# rapidshark-half-assed-half-h-bridge-mk-2.net
KiCad netlist of a schematic drawn in EAGLE
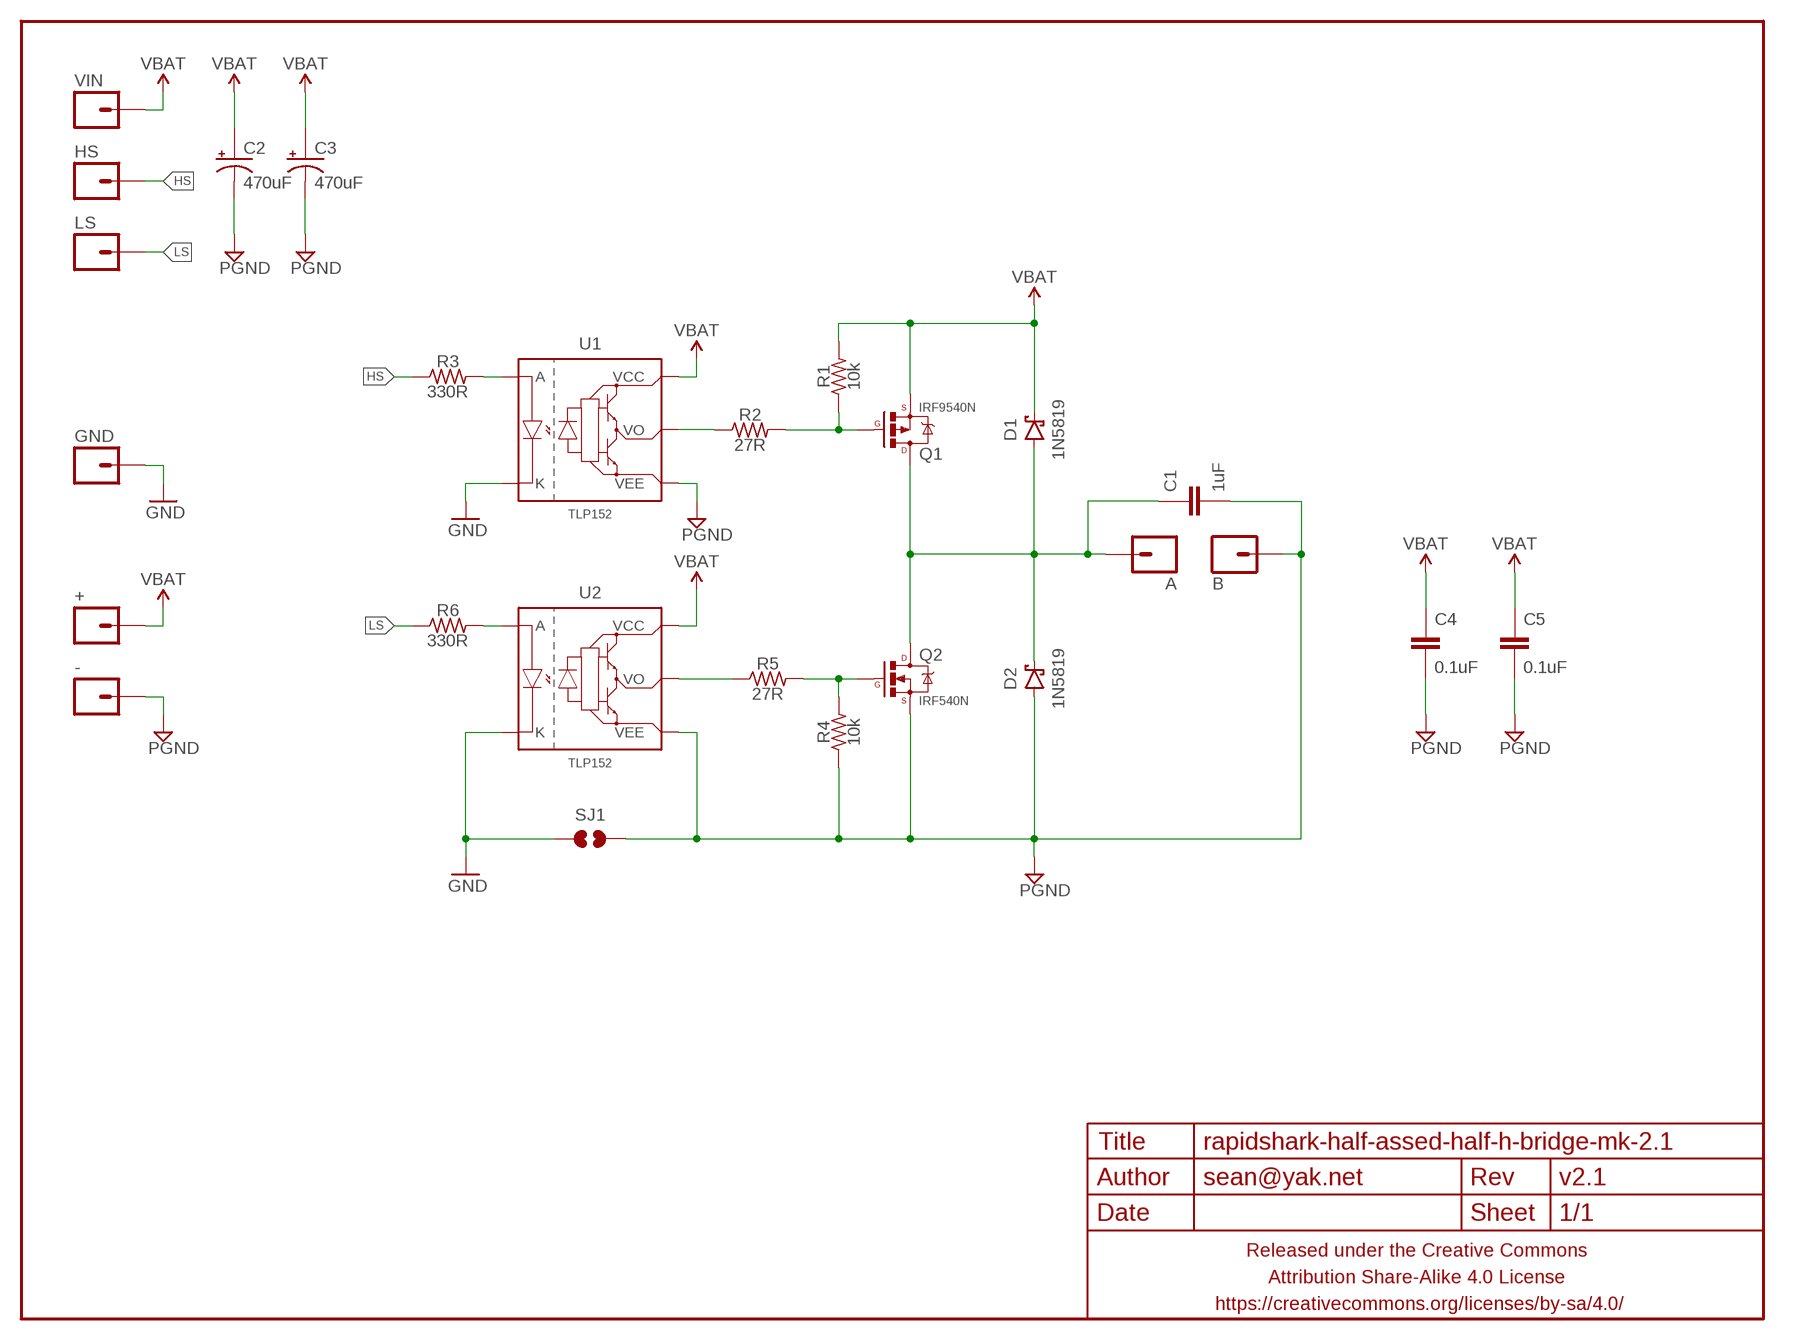
[diagram p0: schematic, sheet 1]

(export (version "E")
  (design (tool "Eeschema 10.0.6"))
  (components
    (comp (ref "+")
      (value "M01PTH-1.9MM")
      (footprint "eagle-import:1X01-1.9MM-CIR")
      (libsource (lib "eagle-import") (part "M01PTH-1.9MM"))
    )
    (comp (ref "-")
      (value "M01PTH-1.9MM")
      (footprint "eagle-import:1X01-1.9MM-CIR")
      (libsource (lib "eagle-import") (part "M01PTH-1.9MM"))
    )
    (comp (ref "A")
      (value "M01PTH-1.9MM")
      (footprint "eagle-import:1X01-1.9MM-CIR")
      (libsource (lib "eagle-import") (part "M01PTH-1.9MM"))
    )
    (comp (ref "B")
      (value "M01PTH-1.9MM")
      (footprint "eagle-import:1X01-1.9MM-CIR")
      (libsource (lib "eagle-import") (part "M01PTH-1.9MM"))
    )
    (comp (ref "C1")
      (value "1uF")
      (footprint "eagle-import:C0603-TIGHTER")
      (libsource (lib "eagle-import") (part "CAPACITOR-CERAMICC0603-TIGHTER"))
    )
    (comp (ref "C2")
      (value "470uF")
      (footprint "eagle-import:E5-10,5")
      (libsource (lib "eagle-import") (part "CAPACITOR-POLARIZEDE5-10.5"))
    )
    (comp (ref "C3")
      (value "470uF")
      (footprint "eagle-import:E5-10,5")
      (libsource (lib "eagle-import") (part "CAPACITOR-POLARIZEDE5-10.5"))
    )
    (comp (ref "C4")
      (value "0.1uF")
      (footprint "eagle-import:C0603-TIGHTER")
      (libsource (lib "eagle-import") (part "CAPACITOR-CERAMICC0603-TIGHTER"))
    )
    (comp (ref "C5")
      (value "0.1uF")
      (footprint "eagle-import:C0603-TIGHTER")
      (libsource (lib "eagle-import") (part "CAPACITOR-CERAMICC0603-TIGHTER"))
    )
    (comp (ref "D1")
      (value "1N5819")
      (footprint "eagle-import:SMA-DIODE-SCHOTTKY")
      (libsource (lib "eagle-import") (part "DIODE-SCHOTTKYSMA"))
    )
    (comp (ref "D2")
      (value "1N5819")
      (footprint "eagle-import:SMA-DIODE-SCHOTTKY")
      (libsource (lib "eagle-import") (part "DIODE-SCHOTTKYSMA"))
    )
    (comp (ref "FRAME1")
      (value "FRAME-LETTERNO_PACKAGE")
      (footprint "eagle-import:DUMMY")
      (fields (field (name "DESIGNER") "sean@yak.net") (field (name "VERSION") "v2.1"))
      (libsource (lib "eagle-import") (part "FRAME-LETTERNO_PACKAGE"))
    )
    (comp (ref "GND")
      (value "M01PTH")
      (footprint "eagle-import:1X01")
      (libsource (lib "eagle-import") (part "M01PTH"))
    )
    (comp (ref "HS")
      (value "M01PTH")
      (footprint "eagle-import:1X01")
      (libsource (lib "eagle-import") (part "M01PTH"))
    )
    (comp (ref "LS")
      (value "M01PTH")
      (footprint "eagle-import:1X01")
      (libsource (lib "eagle-import") (part "M01PTH"))
    )
    (comp (ref "Q1")
      (value "IRF9540N")
      (footprint "eagle-import:D2PAK")
      (libsource (lib "eagle-import") (part "MOSFET-PCHANNELD2PAK"))
    )
    (comp (ref "Q2")
      (value "IRF540N")
      (footprint "eagle-import:D2PAK")
      (libsource (lib "eagle-import") (part "MOSFET-NCHANNELD2PAK"))
    )
    (comp (ref "R1")
      (value "10k")
      (footprint "eagle-import:R0603-TIGHTER")
      (libsource (lib "eagle-import") (part "RESISTORR0603-TIGHTER"))
    )
    (comp (ref "R2")
      (value "27R")
      (footprint "eagle-import:R0603-TIGHTER")
      (libsource (lib "eagle-import") (part "RESISTORR0603-TIGHTER"))
    )
    (comp (ref "R3")
      (value "330R")
      (footprint "eagle-import:R0603-TIGHTER")
      (libsource (lib "eagle-import") (part "RESISTORR0603-TIGHTER"))
    )
    (comp (ref "R4")
      (value "10k")
      (footprint "eagle-import:R0603-TIGHTER")
      (libsource (lib "eagle-import") (part "RESISTORR0603-TIGHTER"))
    )
    (comp (ref "R5")
      (value "27R")
      (footprint "eagle-import:R0603-TIGHTER")
      (libsource (lib "eagle-import") (part "RESISTORR0603-TIGHTER"))
    )
    (comp (ref "R6")
      (value "330R")
      (footprint "eagle-import:R0603-TIGHTER")
      (libsource (lib "eagle-import") (part "RESISTORR0603-TIGHTER"))
    )
    (comp (ref "SJ1")
      (value "JUMPER-PAD-2-NO")
      (footprint "eagle-import:PAD-JUMPER-2-NO_NO_SILK")
      (libsource (lib "eagle-import") (part "JUMPER-PAD-2-NO"))
    )
    (comp (ref "U1")
      (value "TLP152")
      (footprint "eagle-import:SO05")
      (libsource (lib "eagle-import") (part "OPTOISOLATOR-GATEDRIVERSOIC05"))
    )
    (comp (ref "U2")
      (value "TLP152")
      (footprint "eagle-import:SO05")
      (libsource (lib "eagle-import") (part "OPTOISOLATOR-GATEDRIVERSOIC05"))
    )
    (comp (ref "VIN")
      (value "M01PTH")
      (footprint "eagle-import:1X01")
      (libsource (lib "eagle-import") (part "M01PTH"))
    )
  )
  (nets
    (net (code "1") (name "GND") (class "Default")
      (node (ref "GND") (pin "1") (pinfunction "1_1") (pintype "passive"))
      (node (ref "SJ1") (pin "1") (pinfunction "1_1") (pintype "passive"))
      (node (ref "U1") (pin "3") (pinfunction "K_3") (pintype "bidirectional"))
      (node (ref "U2") (pin "3") (pinfunction "K_3") (pintype "bidirectional"))
    )
    (net (code "2") (name "HS") (class "Default")
      (node (ref "HS") (pin "1") (pinfunction "1_1") (pintype "passive"))
      (node (ref "R3") (pin "1") (pinfunction "1_1") (pintype "passive"))
    )
    (net (code "3") (name "LS") (class "Default")
      (node (ref "LS") (pin "1") (pinfunction "1_1") (pintype "passive"))
      (node (ref "R6") (pin "1") (pinfunction "1_1") (pintype "passive"))
    )
    (net (code "4") (name "Net-(A-1)") (class "Default")
      (node (ref "A") (pin "P$1") (pinfunction "1_P$1") (pintype "passive"))
      (node (ref "C1") (pin "1") (pinfunction "1_1") (pintype "passive"))
      (node (ref "D1") (pin "A") (pinfunction "A_A") (pintype "passive"))
      (node (ref "D2") (pin "C") (pinfunction "C_C") (pintype "passive"))
      (node (ref "Q1") (pin "D") (pinfunction "D_D") (pintype "passive"))
      (node (ref "Q2") (pin "D") (pinfunction "D_D") (pintype "passive"))
    )
    (net (code "5") (name "Net-(Q1-PadG)") (class "Default")
      (node (ref "Q1") (pin "G") (pinfunction "G_G") (pintype "passive"))
      (node (ref "R1") (pin "1") (pinfunction "1_1") (pintype "passive"))
      (node (ref "R2") (pin "2") (pinfunction "2_2") (pintype "passive"))
    )
    (net (code "6") (name "Net-(Q2-PadG)") (class "Default")
      (node (ref "Q2") (pin "G") (pinfunction "G_G") (pintype "passive"))
      (node (ref "R4") (pin "2") (pinfunction "2_2") (pintype "passive"))
      (node (ref "R5") (pin "2") (pinfunction "2_2") (pintype "passive"))
    )
    (net (code "7") (name "Net-(U1-A)") (class "Default")
      (node (ref "R3") (pin "2") (pinfunction "2_2") (pintype "passive"))
      (node (ref "U1") (pin "1") (pinfunction "A_1") (pintype "bidirectional"))
    )
    (net (code "8") (name "Net-(U1-VO)") (class "Default")
      (node (ref "R2") (pin "1") (pinfunction "1_1") (pintype "passive"))
      (node (ref "U1") (pin "5") (pinfunction "VO_5") (pintype "bidirectional"))
    )
    (net (code "9") (name "Net-(U2-A)") (class "Default")
      (node (ref "R6") (pin "2") (pinfunction "2_2") (pintype "passive"))
      (node (ref "U2") (pin "1") (pinfunction "A_1") (pintype "bidirectional"))
    )
    (net (code "10") (name "Net-(U2-VO)") (class "Default")
      (node (ref "R5") (pin "1") (pinfunction "1_1") (pintype "passive"))
      (node (ref "U2") (pin "5") (pinfunction "VO_5") (pintype "bidirectional"))
    )
    (net (code "11") (name "PGND") (class "Default")
      (node (ref "-") (pin "P$1") (pinfunction "1_P$1") (pintype "passive"))
      (node (ref "B") (pin "P$1") (pinfunction "1_P$1") (pintype "passive"))
      (node (ref "C1") (pin "2") (pinfunction "2_2") (pintype "passive"))
      (node (ref "C2") (pin "-") (pinfunction "-_-") (pintype "passive"))
      (node (ref "C3") (pin "-") (pinfunction "-_-") (pintype "passive"))
      (node (ref "C4") (pin "2") (pinfunction "2_2") (pintype "passive"))
      (node (ref "C5") (pin "2") (pinfunction "2_2") (pintype "passive"))
      (node (ref "D2") (pin "A") (pinfunction "A_A") (pintype "passive"))
      (node (ref "Q2") (pin "S") (pinfunction "S_S") (pintype "passive"))
      (node (ref "R4") (pin "1") (pinfunction "1_1") (pintype "passive"))
      (node (ref "SJ1") (pin "2") (pinfunction "2_2") (pintype "passive"))
      (node (ref "U1") (pin "4") (pinfunction "VEE_4") (pintype "bidirectional"))
      (node (ref "U2") (pin "4") (pinfunction "VEE_4") (pintype "bidirectional"))
    )
    (net (code "12") (name "VBAT") (class "Default")
      (node (ref "+") (pin "P$1") (pinfunction "1_P$1") (pintype "passive"))
      (node (ref "C2") (pin "+") (pinfunction "+_+") (pintype "passive"))
      (node (ref "C3") (pin "+") (pinfunction "+_+") (pintype "passive"))
      (node (ref "C4") (pin "1") (pinfunction "1_1") (pintype "passive"))
      (node (ref "C5") (pin "1") (pinfunction "1_1") (pintype "passive"))
      (node (ref "D1") (pin "C") (pinfunction "C_C") (pintype "passive"))
      (node (ref "Q1") (pin "S") (pinfunction "S_S") (pintype "passive"))
      (node (ref "R1") (pin "2") (pinfunction "2_2") (pintype "passive"))
      (node (ref "U1") (pin "6") (pinfunction "VCC_6") (pintype "bidirectional"))
      (node (ref "U2") (pin "6") (pinfunction "VCC_6") (pintype "bidirectional"))
      (node (ref "VIN") (pin "1") (pinfunction "1_1") (pintype "passive"))
    )
  )
)
